# attiniest85-light-sensor-shield-mk-1_0.net
KiCad netlist of a schematic drawn in EAGLE
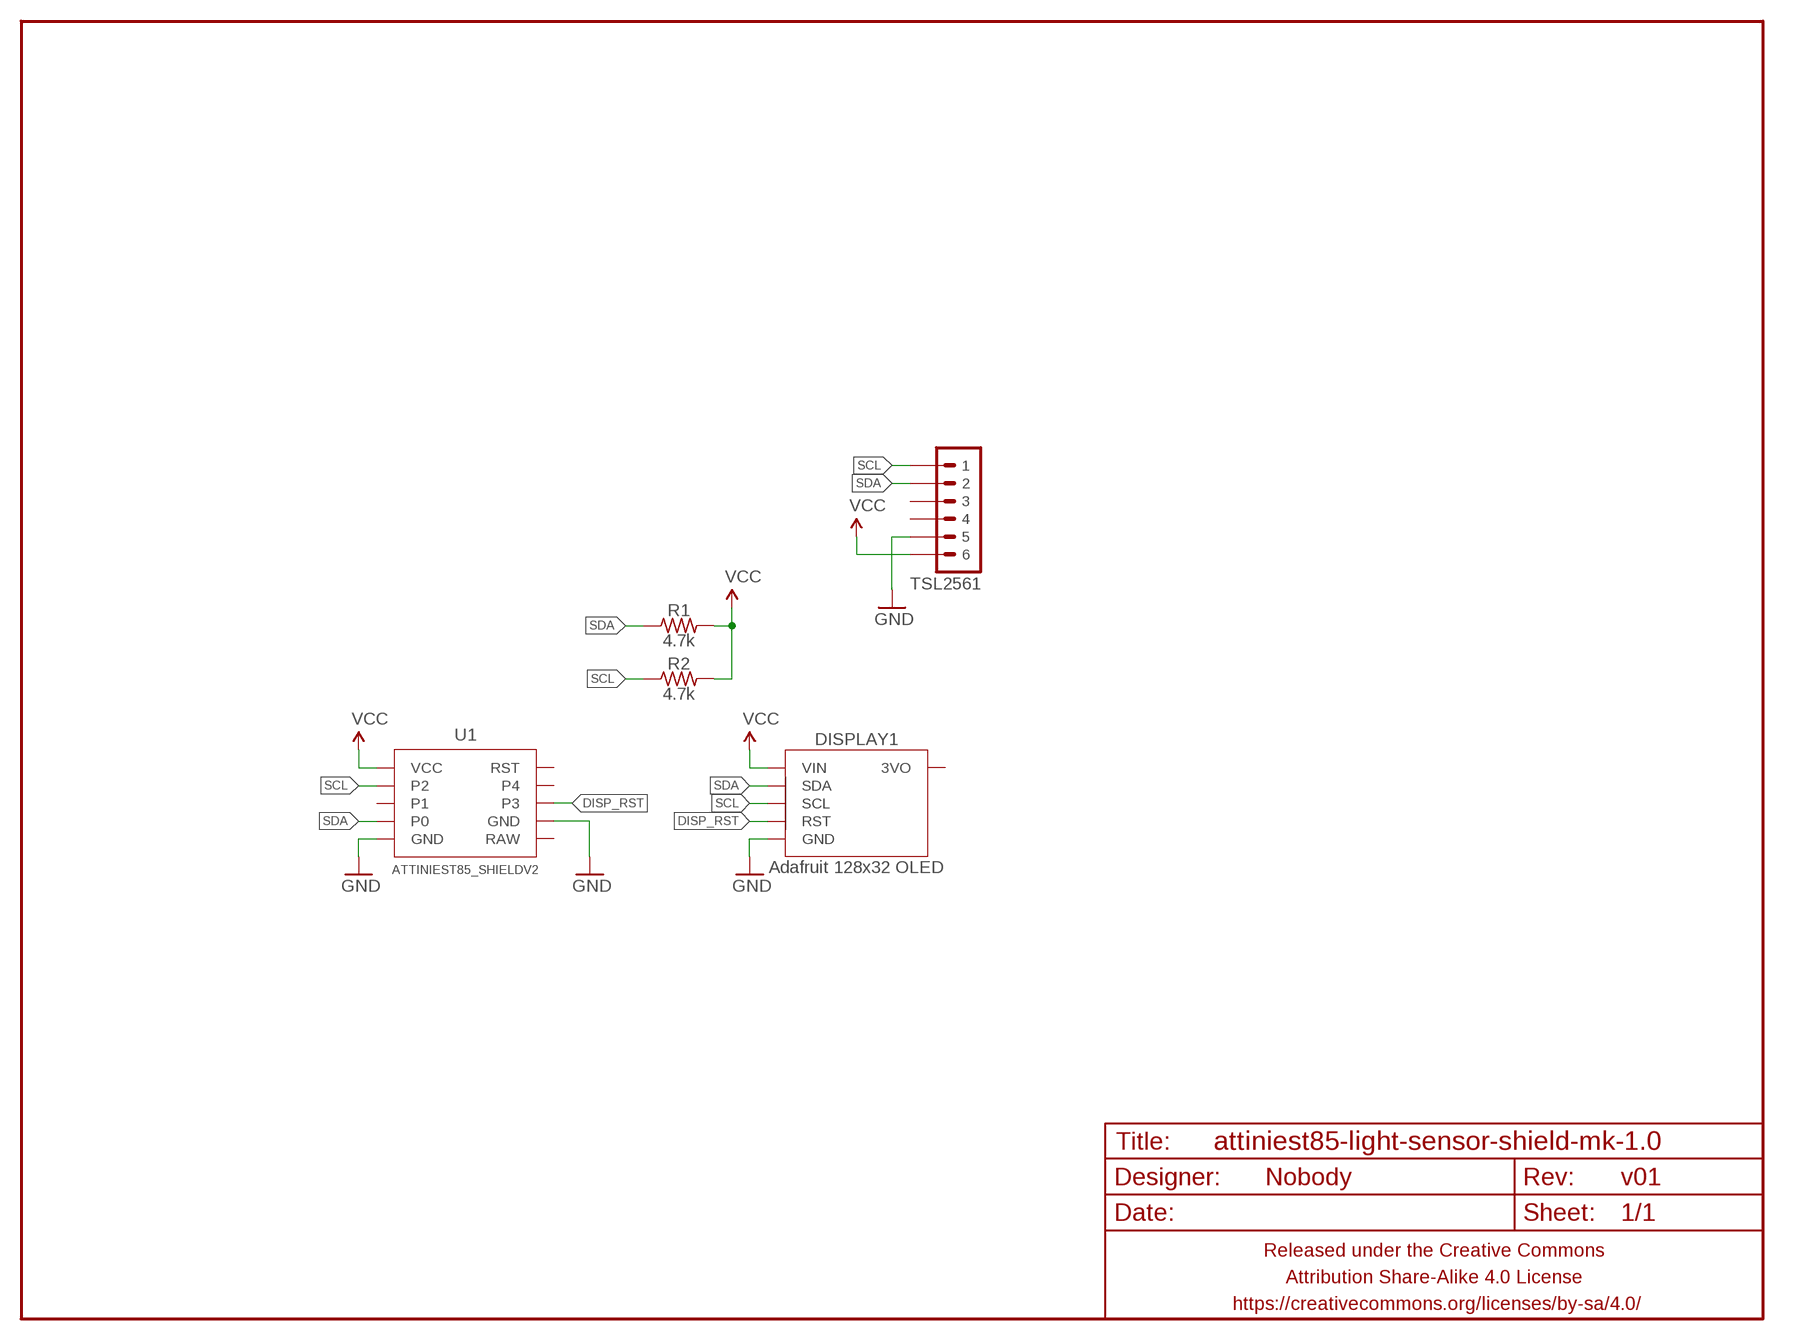
[diagram p0: schematic, sheet 1]

(export (version "E")
  (design (tool "Eeschema 10.0.6"))
  (components
    (comp (ref "DISPLAY1")
      (value "Adafruit 128x32 OLED")
      (footprint "eagle-import:ADAFRUIT_128X32_OLED_I2C_CLOSER_NOHOLES")
      (libsource (lib "eagle-import") (part "ADAFRUIT_128X32_OLED_I2CNOHOLES"))
    )
    (comp (ref "FRAME1")
      (value "FRAME-LETTERNO_PACKAGE")
      (footprint "eagle-import:DUMMY")
      (fields (field (name "DESIGNER") "Nobody"))
      (libsource (lib "eagle-import") (part "FRAME-LETTERNO_PACKAGE"))
    )
    (comp (ref "R1")
      (value "4.7k")
      (footprint "eagle-import:RESISTOR-AXIAL-PTH-7.62MM")
      (libsource (lib "eagle-import") (part "RESISTORPTH-AXIAL-7.62MM"))
    )
    (comp (ref "R2")
      (value "4.7k")
      (footprint "eagle-import:RESISTOR-AXIAL-PTH-7.62MM")
      (libsource (lib "eagle-import") (part "RESISTORPTH-AXIAL-7.62MM"))
    )
    (comp (ref "TSL2561")
      (value "M06CLOSER")
      (footprint "eagle-import:1X06_CLOSER")
      (libsource (lib "eagle-import") (part "M06CLOSER"))
    )
    (comp (ref "U1")
      (value "ATTINIEST85_SHIELDV2")
      (footprint "eagle-import:ATTINIEST85_SHIELD_V2")
      (libsource (lib "eagle-import") (part "ATTINIEST85_SHIELDV2"))
    )
  )
  (nets
    (net (code "1") (name "DISP_RST") (class "Default")
      (node (ref "DISPLAY1") (pin "RST") (pinfunction "RST_RST") (pintype "bidirectional"))
      (node (ref "U1") (pin "3") (pinfunction "P3_3") (pintype "bidirectional"))
    )
    (net (code "2") (name "GND") (class "Default")
      (node (ref "DISPLAY1") (pin "GND") (pinfunction "GND_GND") (pintype "bidirectional"))
      (node (ref "TSL2561") (pin "5") (pinfunction "5_5") (pintype "passive"))
      (node (ref "U1") (pin "GND@1") (pinfunction "GND_GND@1") (pintype "bidirectional"))
      (node (ref "U1") (pin "GND@2") (pinfunction "GND_GND@2") (pintype "bidirectional"))
    )
    (net (code "3") (name "SCL") (class "Default")
      (node (ref "DISPLAY1") (pin "SCL") (pinfunction "SCL_SCL") (pintype "bidirectional"))
      (node (ref "R2") (pin "P$1") (pinfunction "1_P$1") (pintype "passive"))
      (node (ref "TSL2561") (pin "1") (pinfunction "1_1") (pintype "passive"))
      (node (ref "U1") (pin "2") (pinfunction "P2_2") (pintype "bidirectional"))
    )
    (net (code "4") (name "SDA") (class "Default")
      (node (ref "DISPLAY1") (pin "SDA") (pinfunction "SDA_SDA") (pintype "bidirectional"))
      (node (ref "R1") (pin "P$1") (pinfunction "1_P$1") (pintype "passive"))
      (node (ref "TSL2561") (pin "2") (pinfunction "2_2") (pintype "passive"))
      (node (ref "U1") (pin "0") (pinfunction "P0_0") (pintype "bidirectional"))
    )
    (net (code "5") (name "VCC") (class "Default")
      (node (ref "DISPLAY1") (pin "VIN") (pinfunction "VIN_VIN") (pintype "bidirectional"))
      (node (ref "R1") (pin "P$2") (pinfunction "2_P$2") (pintype "passive"))
      (node (ref "R2") (pin "P$2") (pinfunction "2_P$2") (pintype "passive"))
      (node (ref "TSL2561") (pin "6") (pinfunction "6_6") (pintype "passive"))
      (node (ref "U1") (pin "VCC") (pinfunction "VCC_VCC") (pintype "bidirectional"))
    )
    (net (code "6") (name "unconnected-(DISPLAY1-Pad3VO)") (class "Default")
      (node (ref "DISPLAY1") (pin "3VO") (pinfunction "3VO_3VO") (pintype "bidirectional"))
    )
    (net (code "7") (name "unconnected-(TSL2561-Pad3)") (class "Default")
      (node (ref "TSL2561") (pin "3") (pinfunction "3_3") (pintype "passive"))
    )
    (net (code "8") (name "unconnected-(TSL2561-Pad4)") (class "Default")
      (node (ref "TSL2561") (pin "4") (pinfunction "4_4") (pintype "passive"))
    )
    (net (code "9") (name "unconnected-(U1-P1-Pad1)") (class "Default")
      (node (ref "U1") (pin "1") (pinfunction "P1_1") (pintype "bidirectional"))
    )
    (net (code "10") (name "unconnected-(U1-P4-Pad4)") (class "Default")
      (node (ref "U1") (pin "4") (pinfunction "P4_4") (pintype "bidirectional"))
    )
    (net (code "11") (name "unconnected-(U1-PadRAW)") (class "Default")
      (node (ref "U1") (pin "RAW") (pinfunction "RAW_RAW") (pintype "bidirectional"))
    )
    (net (code "12") (name "unconnected-(U1-PadRST)") (class "Default")
      (node (ref "U1") (pin "RST") (pinfunction "RST_RST") (pintype "bidirectional"))
    )
  )
)
